# Power_Supply_Schematic.net
KiCad netlist of a schematic drawn in Altium Designer
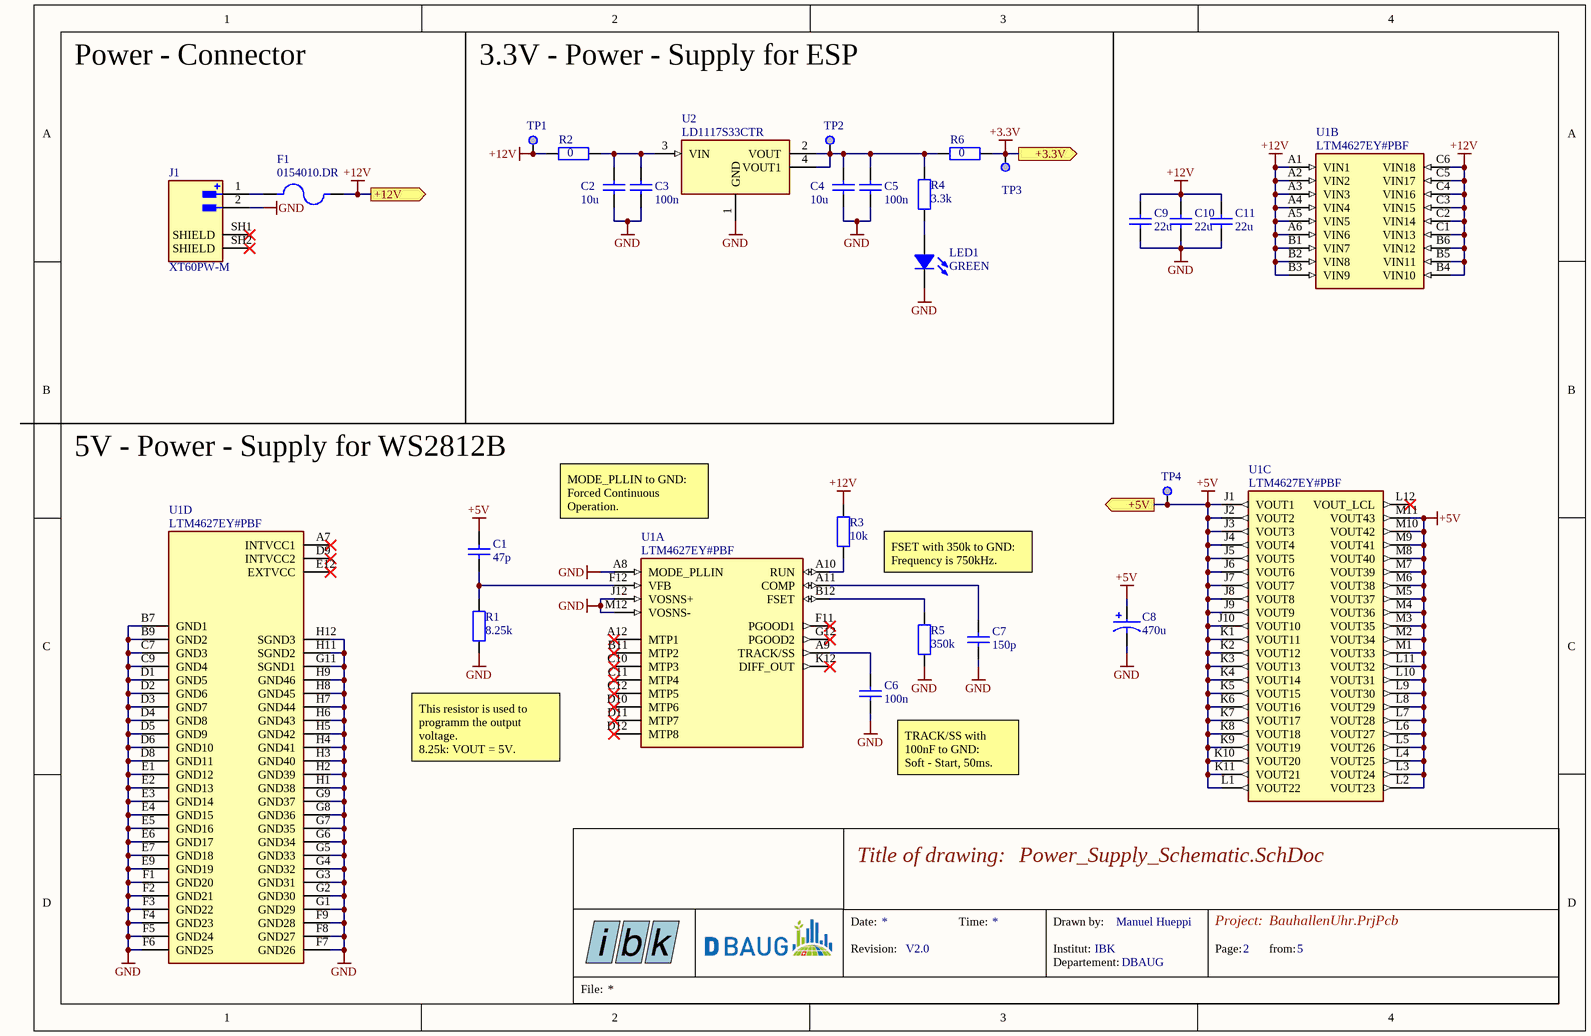
[diagram p0: Power_Supply_Schematic.SchDoc]

(export (version "E")
  (design (tool "Eeschema 10.0.6"))
  (components
    (comp (ref "C1")
      (value "47p")
      (footprint "PCB_Altium_Library_Manuel:0603_CAPACITOR")
      (description "0603")
      (libsource (lib "Schematic_Altium_Library_Manuel") (part "Capacitor"))
    )
    (comp (ref "C2")
      (value "10u")
      (footprint "PCB_Altium_Library_Manuel:Capacitor_0805")
      (description "0805")
      (libsource (lib "Schematic_Altium_Library_Manuel") (part "Capacitor_0805"))
    )
    (comp (ref "C3")
      (value "100n")
      (footprint "PCB_Altium_Library_Manuel:0603_CAPACITOR")
      (description "0603")
      (libsource (lib "Schematic_Altium_Library_Manuel") (part "Capacitor"))
    )
    (comp (ref "C4")
      (value "10u")
      (footprint "PCB_Altium_Library_Manuel:Capacitor_0805")
      (description "0805")
      (libsource (lib "Schematic_Altium_Library_Manuel") (part "Capacitor_0805"))
    )
    (comp (ref "C5")
      (value "100n")
      (footprint "PCB_Altium_Library_Manuel:0603_CAPACITOR")
      (description "0603")
      (libsource (lib "Schematic_Altium_Library_Manuel") (part "Capacitor"))
    )
    (comp (ref "C6")
      (value "100n")
      (footprint "PCB_Altium_Library_Manuel:0603_CAPACITOR")
      (description "0603")
      (libsource (lib "Schematic_Altium_Library_Manuel") (part "Capacitor"))
    )
    (comp (ref "C7")
      (value "150p")
      (footprint "PCB_Altium_Library_Manuel:0603_CAPACITOR")
      (description "0603")
      (libsource (lib "Schematic_Altium_Library_Manuel") (part "Capacitor"))
    )
    (comp (ref "C8")
      (value "470u")
      (footprint "PCB_Altium_Library_Manuel:Capacitor_Tantalum")
      (description "470 µF Molded Tantalum Capacitors 6.3 V 2917 (7343 Metric) 100mOhm.")
      (libsource (lib "Schematic_Altium_Library_Manuel") (part "Capacitor_Tantalum"))
    )
    (comp (ref "C9")
      (value "22u")
      (footprint "PCB_Altium_Library_Manuel:Capacitor_0805")
      (description "0805")
      (libsource (lib "Schematic_Altium_Library_Manuel") (part "Capacitor_0805"))
    )
    (comp (ref "C10")
      (value "22u")
      (footprint "PCB_Altium_Library_Manuel:Capacitor_0805")
      (description "0805")
      (libsource (lib "Schematic_Altium_Library_Manuel") (part "Capacitor_0805"))
    )
    (comp (ref "C11")
      (value "22u")
      (footprint "PCB_Altium_Library_Manuel:Capacitor_0805")
      (description "0805")
      (libsource (lib "Schematic_Altium_Library_Manuel") (part "Capacitor_0805"))
    )
    (comp (ref "F1")
      (value "0154010.DR")
      (footprint "PCB_Altium_Library_Manuel:Fuse")
      (description "FUSE BRD MNT 10A 125VAC/VDC SMD ¦ Littelfuse 0154010.DR.")
      (libsource (lib "Schematic_Altium_Library_Manuel") (part "Fuse"))
    )
    (comp (ref "J1")
      (value "XT60PW-M")
      (footprint "PCB_Altium_Library_Manuel:PCB_Connector")
      (description "Socket, DC supply, male, PIN: 2.")
      (fields (field (name "MF") "AMASS"))
      (libsource (lib "Schematic_Altium_Library_Manuel") (part "PCB_Connector"))
    )
    (comp (ref "LED1")
      (value "GREEN")
      (footprint "PCB_Altium_Library_Manuel:LED_0603, GREEN")
      (description "LED 0603, Green, 3.2 V, 20 mA, 430 mcd")
      (libsource (lib "Schematic_Altium_Library_Manuel") (part "LED_0603, GREEN"))
    )
    (comp (ref "R1")
      (value "8.25k")
      (footprint "PCB_Altium_Library_Manuel:Resistor_0603")
      (description "0603")
      (libsource (lib "Schematic_Altium_Library_Manuel") (part "Resistor_0603"))
    )
    (comp (ref "R2")
      (value "0")
      (footprint "PCB_Altium_Library_Manuel:1206_Resistor")
      (description "1206")
      (libsource (lib "Schematic_Altium_Library_Manuel") (part "Resistor_1206"))
    )
    (comp (ref "R3")
      (value "10k")
      (footprint "PCB_Altium_Library_Manuel:Resistor_0603")
      (description "0603")
      (libsource (lib "Schematic_Altium_Library_Manuel") (part "Resistor_0603"))
    )
    (comp (ref "R4")
      (value "3.3k")
      (footprint "PCB_Altium_Library_Manuel:Resistor_0603")
      (description "0603")
      (libsource (lib "Schematic_Altium_Library_Manuel") (part "Resistor_0603"))
    )
    (comp (ref "R5")
      (value "350k")
      (footprint "PCB_Altium_Library_Manuel:Resistor_0603")
      (description "0603")
      (libsource (lib "Schematic_Altium_Library_Manuel") (part "Resistor_0603"))
    )
    (comp (ref "R6")
      (value "0")
      (footprint "PCB_Altium_Library_Manuel:1206_Resistor")
      (description "1206")
      (libsource (lib "Schematic_Altium_Library_Manuel") (part "Resistor_1206"))
    )
    (comp (ref "TP1")
      (value "Testpoint S2761-46R")
      (footprint "PCB_Altium_Library_Manuel:Testpoint S2761-46R")
      (description "Prüfstecker und Messbuchsen EZ BoardWare S27 SMT Mini Test Terminal, Reel")
      (libsource (lib "Schematic_Altium_Library_Manuel") (part "Testpoint S2761-46R"))
    )
    (comp (ref "TP2")
      (value "Testpoint S2761-46R")
      (footprint "PCB_Altium_Library_Manuel:Testpoint S2761-46R")
      (description "Prüfstecker und Messbuchsen EZ BoardWare S27 SMT Mini Test Terminal, Reel")
      (libsource (lib "Schematic_Altium_Library_Manuel") (part "Testpoint S2761-46R"))
    )
    (comp (ref "TP3")
      (value "Testpoint S2761-46R")
      (footprint "PCB_Altium_Library_Manuel:Testpoint S2761-46R")
      (description "Prüfstecker und Messbuchsen EZ BoardWare S27 SMT Mini Test Terminal, Reel")
      (libsource (lib "Schematic_Altium_Library_Manuel") (part "Testpoint S2761-46R"))
    )
    (comp (ref "TP4")
      (value "Testpoint S2761-46R")
      (footprint "PCB_Altium_Library_Manuel:Testpoint S2761-46R")
      (description "Prüfstecker und Messbuchsen EZ BoardWare S27 SMT Mini Test Terminal, Reel")
      (libsource (lib "Schematic_Altium_Library_Manuel") (part "Testpoint S2761-46R"))
    )
    (comp (ref "U1")
      (value "LTM4627EY#PBF")
      (footprint "PCB_Altium_Library_Manuel:DCDC_Converter")
      (description "Module DC-DC 1-OUT 0.6V to 5V 15A Automotive 133-Pin BGA Tray.")
      (fields (field (name "MF") "Analog Devices"))
      (libsource (lib "Schematic_Altium_Library_Manuel") (part "DCDC_Converter"))
    )
    (comp (ref "U2")
      (value "LD1117S33CTR")
      (footprint "PCB_Altium_Library_Manuel:LD1117S33CTR")
      (description "LDO, 3.3V and 800mA.")
      (libsource (lib "Schematic_Altium_Library_Manuel") (part "LD1117S33CTR"))
    )
  )
  (nets
    (net (code "1") (name "+3.3V") (class "Default")
      (node (ref "R6") (pin "2") (pinfunction "2_2") (pintype "passive"))
      (node (ref "TP3") (pin "1") (pinfunction "1_1") (pintype "passive"))
    )
    (net (code "2") (name "+5V") (class "Default")
      (node (ref "C1") (pin "2") (pinfunction "2_2") (pintype "passive"))
      (node (ref "C8") (pin "1") (pinfunction "1_1") (pintype "passive"))
      (node (ref "TP4") (pin "1") (pinfunction "1_1") (pintype "passive"))
      (node (ref "U1") (pin "J1") (pinfunction "VOUT1_J1") (pintype "output"))
      (node (ref "U1") (pin "J10") (pinfunction "VOUT10_J10") (pintype "output"))
      (node (ref "U1") (pin "J2") (pinfunction "VOUT2_J2") (pintype "output"))
      (node (ref "U1") (pin "J3") (pinfunction "VOUT3_J3") (pintype "output"))
      (node (ref "U1") (pin "J4") (pinfunction "VOUT4_J4") (pintype "output"))
      (node (ref "U1") (pin "J5") (pinfunction "VOUT5_J5") (pintype "output"))
      (node (ref "U1") (pin "J6") (pinfunction "VOUT6_J6") (pintype "output"))
      (node (ref "U1") (pin "J7") (pinfunction "VOUT7_J7") (pintype "output"))
      (node (ref "U1") (pin "J8") (pinfunction "VOUT8_J8") (pintype "output"))
      (node (ref "U1") (pin "J9") (pinfunction "VOUT9_J9") (pintype "output"))
      (node (ref "U1") (pin "K1") (pinfunction "VOUT11_K1") (pintype "output"))
      (node (ref "U1") (pin "K10") (pinfunction "VOUT20_K10") (pintype "output"))
      (node (ref "U1") (pin "K11") (pinfunction "VOUT21_K11") (pintype "output"))
      (node (ref "U1") (pin "K2") (pinfunction "VOUT12_K2") (pintype "output"))
      (node (ref "U1") (pin "K3") (pinfunction "VOUT13_K3") (pintype "output"))
      (node (ref "U1") (pin "K4") (pinfunction "VOUT14_K4") (pintype "output"))
      (node (ref "U1") (pin "K5") (pinfunction "VOUT15_K5") (pintype "output"))
      (node (ref "U1") (pin "K6") (pinfunction "VOUT16_K6") (pintype "output"))
      (node (ref "U1") (pin "K7") (pinfunction "VOUT17_K7") (pintype "output"))
      (node (ref "U1") (pin "K8") (pinfunction "VOUT18_K8") (pintype "output"))
      (node (ref "U1") (pin "K9") (pinfunction "VOUT19_K9") (pintype "output"))
      (node (ref "U1") (pin "L1") (pinfunction "VOUT22_L1") (pintype "output"))
      (node (ref "U1") (pin "L10") (pinfunction "VOUT31_L10") (pintype "output"))
      (node (ref "U1") (pin "L11") (pinfunction "VOUT32_L11") (pintype "output"))
      (node (ref "U1") (pin "L2") (pinfunction "VOUT23_L2") (pintype "output"))
      (node (ref "U1") (pin "L3") (pinfunction "VOUT24_L3") (pintype "output"))
      (node (ref "U1") (pin "L4") (pinfunction "VOUT25_L4") (pintype "output"))
      (node (ref "U1") (pin "L5") (pinfunction "VOUT26_L5") (pintype "output"))
      (node (ref "U1") (pin "L6") (pinfunction "VOUT27_L6") (pintype "output"))
      (node (ref "U1") (pin "L7") (pinfunction "VOUT28_L7") (pintype "output"))
      (node (ref "U1") (pin "L8") (pinfunction "VOUT29_L8") (pintype "output"))
      (node (ref "U1") (pin "L9") (pinfunction "VOUT30_L9") (pintype "output"))
      (node (ref "U1") (pin "M1") (pinfunction "VOUT33_M1") (pintype "output"))
      (node (ref "U1") (pin "M10") (pinfunction "VOUT42_M10") (pintype "output"))
      (node (ref "U1") (pin "M11") (pinfunction "VOUT43_M11") (pintype "output"))
      (node (ref "U1") (pin "M2") (pinfunction "VOUT34_M2") (pintype "output"))
      (node (ref "U1") (pin "M3") (pinfunction "VOUT35_M3") (pintype "output"))
      (node (ref "U1") (pin "M4") (pinfunction "VOUT36_M4") (pintype "output"))
      (node (ref "U1") (pin "M5") (pinfunction "VOUT37_M5") (pintype "output"))
      (node (ref "U1") (pin "M6") (pinfunction "VOUT38_M6") (pintype "output"))
      (node (ref "U1") (pin "M7") (pinfunction "VOUT39_M7") (pintype "output"))
      (node (ref "U1") (pin "M8") (pinfunction "VOUT40_M8") (pintype "output"))
      (node (ref "U1") (pin "M9") (pinfunction "VOUT41_M9") (pintype "output"))
    )
    (net (code "3") (name "+12V") (class "Default")
      (node (ref "C10") (pin "2") (pinfunction "2_2") (pintype "passive"))
      (node (ref "C11") (pin "2") (pinfunction "2_2") (pintype "passive"))
      (node (ref "C9") (pin "2") (pinfunction "2_2") (pintype "passive"))
      (node (ref "F1") (pin "2") (pinfunction "2_2") (pintype "passive"))
      (node (ref "R2") (pin "1") (pinfunction "1_1") (pintype "passive"))
      (node (ref "R3") (pin "2") (pinfunction "2_2") (pintype "passive"))
      (node (ref "TP1") (pin "1") (pinfunction "1_1") (pintype "passive"))
      (node (ref "U1") (pin "A1") (pinfunction "VIN1_A1") (pintype "input"))
      (node (ref "U1") (pin "A2") (pinfunction "VIN2_A2") (pintype "input"))
      (node (ref "U1") (pin "A3") (pinfunction "VIN3_A3") (pintype "input"))
      (node (ref "U1") (pin "A4") (pinfunction "VIN4_A4") (pintype "input"))
      (node (ref "U1") (pin "A5") (pinfunction "VIN5_A5") (pintype "input"))
      (node (ref "U1") (pin "A6") (pinfunction "VIN6_A6") (pintype "input"))
      (node (ref "U1") (pin "B1") (pinfunction "VIN7_B1") (pintype "input"))
      (node (ref "U1") (pin "B2") (pinfunction "VIN8_B2") (pintype "input"))
      (node (ref "U1") (pin "B3") (pinfunction "VIN9_B3") (pintype "input"))
      (node (ref "U1") (pin "B4") (pinfunction "VIN10_B4") (pintype "input"))
      (node (ref "U1") (pin "B5") (pinfunction "VIN11_B5") (pintype "input"))
      (node (ref "U1") (pin "B6") (pinfunction "VIN12_B6") (pintype "input"))
      (node (ref "U1") (pin "C1") (pinfunction "VIN13_C1") (pintype "input"))
      (node (ref "U1") (pin "C2") (pinfunction "VIN14_C2") (pintype "input"))
      (node (ref "U1") (pin "C3") (pinfunction "VIN15_C3") (pintype "input"))
      (node (ref "U1") (pin "C4") (pinfunction "VIN16_C4") (pintype "input"))
      (node (ref "U1") (pin "C5") (pinfunction "VIN17_C5") (pintype "input"))
      (node (ref "U1") (pin "C6") (pinfunction "VIN18_C6") (pintype "input"))
    )
    (net (code "4") (name "GND") (class "Default")
      (node (ref "C10") (pin "1") (pinfunction "1_1") (pintype "passive"))
      (node (ref "C11") (pin "1") (pinfunction "1_1") (pintype "passive"))
      (node (ref "C2") (pin "1") (pinfunction "1_1") (pintype "passive"))
      (node (ref "C3") (pin "1") (pinfunction "1_1") (pintype "passive"))
      (node (ref "C4") (pin "1") (pinfunction "1_1") (pintype "passive"))
      (node (ref "C5") (pin "1") (pinfunction "1_1") (pintype "passive"))
      (node (ref "C6") (pin "1") (pinfunction "1_1") (pintype "passive"))
      (node (ref "C7") (pin "1") (pinfunction "1_1") (pintype "passive"))
      (node (ref "C8") (pin "2") (pinfunction "2_2") (pintype "passive"))
      (node (ref "C9") (pin "1") (pinfunction "1_1") (pintype "passive"))
      (node (ref "J1") (pin "2") (pinfunction "N_2") (pintype "passive"))
      (node (ref "LED1") (pin "K") (pinfunction "K_K") (pintype "passive"))
      (node (ref "R1") (pin "1") (pinfunction "1_1") (pintype "passive"))
      (node (ref "R5") (pin "1") (pinfunction "1_1") (pintype "passive"))
      (node (ref "U1") (pin "A8") (pinfunction "MODE_PLLIN_A8") (pintype "input"))
      (node (ref "U1") (pin "B7") (pinfunction "GND1_B7") (pintype "power_in"))
      (node (ref "U1") (pin "B9") (pinfunction "GND2_B9") (pintype "power_in"))
      (node (ref "U1") (pin "C7") (pinfunction "GND3_C7") (pintype "power_in"))
      (node (ref "U1") (pin "C9") (pinfunction "GND4_C9") (pintype "power_in"))
      (node (ref "U1") (pin "D1") (pinfunction "GND5_D1") (pintype "power_in"))
      (node (ref "U1") (pin "D2") (pinfunction "GND6_D2") (pintype "power_in"))
      (node (ref "U1") (pin "D3") (pinfunction "GND7_D3") (pintype "power_in"))
      (node (ref "U1") (pin "D4") (pinfunction "GND8_D4") (pintype "power_in"))
      (node (ref "U1") (pin "D5") (pinfunction "GND9_D5") (pintype "power_in"))
      (node (ref "U1") (pin "D6") (pinfunction "GND10_D6") (pintype "power_in"))
      (node (ref "U1") (pin "D8") (pinfunction "GND11_D8") (pintype "power_in"))
      (node (ref "U1") (pin "E1") (pinfunction "GND12_E1") (pintype "power_in"))
      (node (ref "U1") (pin "E2") (pinfunction "GND13_E2") (pintype "power_in"))
      (node (ref "U1") (pin "E3") (pinfunction "GND14_E3") (pintype "power_in"))
      (node (ref "U1") (pin "E4") (pinfunction "GND15_E4") (pintype "power_in"))
      (node (ref "U1") (pin "E5") (pinfunction "GND16_E5") (pintype "power_in"))
      (node (ref "U1") (pin "E6") (pinfunction "GND17_E6") (pintype "power_in"))
      (node (ref "U1") (pin "E7") (pinfunction "GND18_E7") (pintype "power_in"))
      (node (ref "U1") (pin "E9") (pinfunction "GND19_E9") (pintype "power_in"))
      (node (ref "U1") (pin "F1") (pinfunction "GND20_F1") (pintype "power_in"))
      (node (ref "U1") (pin "F2") (pinfunction "GND21_F2") (pintype "power_in"))
      (node (ref "U1") (pin "F3") (pinfunction "GND22_F3") (pintype "power_in"))
      (node (ref "U1") (pin "F4") (pinfunction "GND23_F4") (pintype "power_in"))
      (node (ref "U1") (pin "F5") (pinfunction "GND24_F5") (pintype "power_in"))
      (node (ref "U1") (pin "F6") (pinfunction "GND25_F6") (pintype "power_in"))
      (node (ref "U1") (pin "F7") (pinfunction "GND26_F7") (pintype "power_in"))
      (node (ref "U1") (pin "F8") (pinfunction "GND27_F8") (pintype "power_in"))
      (node (ref "U1") (pin "F9") (pinfunction "GND28_F9") (pintype "power_in"))
      (node (ref "U1") (pin "G1") (pinfunction "GND29_G1") (pintype "power_in"))
      (node (ref "U1") (pin "G11") (pinfunction "SGND1_G11") (pintype "power_in"))
      (node (ref "U1") (pin "G2") (pinfunction "GND30_G2") (pintype "power_in"))
      (node (ref "U1") (pin "G3") (pinfunction "GND31_G3") (pintype "power_in"))
      (node (ref "U1") (pin "G4") (pinfunction "GND32_G4") (pintype "power_in"))
      (node (ref "U1") (pin "G5") (pinfunction "GND33_G5") (pintype "power_in"))
      (node (ref "U1") (pin "G6") (pinfunction "GND34_G6") (pintype "power_in"))
      (node (ref "U1") (pin "G7") (pinfunction "GND35_G7") (pintype "power_in"))
      (node (ref "U1") (pin "G8") (pinfunction "GND36_G8") (pintype "power_in"))
      (node (ref "U1") (pin "G9") (pinfunction "GND37_G9") (pintype "power_in"))
      (node (ref "U1") (pin "H1") (pinfunction "GND38_H1") (pintype "power_in"))
      (node (ref "U1") (pin "H11") (pinfunction "SGND2_H11") (pintype "power_in"))
      (node (ref "U1") (pin "H12") (pinfunction "SGND3_H12") (pintype "power_in"))
      (node (ref "U1") (pin "H2") (pinfunction "GND39_H2") (pintype "power_in"))
      (node (ref "U1") (pin "H3") (pinfunction "GND40_H3") (pintype "power_in"))
      (node (ref "U1") (pin "H4") (pinfunction "GND41_H4") (pintype "power_in"))
      (node (ref "U1") (pin "H5") (pinfunction "GND42_H5") (pintype "power_in"))
      (node (ref "U1") (pin "H6") (pinfunction "GND43_H6") (pintype "power_in"))
      (node (ref "U1") (pin "H7") (pinfunction "GND44_H7") (pintype "power_in"))
      (node (ref "U1") (pin "H8") (pinfunction "GND45_H8") (pintype "power_in"))
      (node (ref "U1") (pin "H9") (pinfunction "GND46_H9") (pintype "power_in"))
      (node (ref "U1") (pin "J12") (pinfunction "VOSNS+_J12") (pintype "input"))
      (node (ref "U1") (pin "M12") (pinfunction "VOSNS-_M12") (pintype "input"))
      (node (ref "U2") (pin "1") (pinfunction "GND_1") (pintype "power_in"))
    )
    (net (code "5") (name "Net-(J1-P)") (class "Default")
      (node (ref "F1") (pin "1") (pinfunction "1_1") (pintype "passive"))
      (node (ref "J1") (pin "1") (pinfunction "P_1") (pintype "passive"))
    )
    (net (code "6") (name "Net-(LED1-PadA)") (class "Default")
      (node (ref "LED1") (pin "A") (pinfunction "A_A") (pintype "passive"))
      (node (ref "R4") (pin "1") (pinfunction "1_1") (pintype "passive"))
    )
    (net (code "7") (name "Net-(U1A-COMP)") (class "Default")
      (node (ref "C7") (pin "2") (pinfunction "2_2") (pintype "passive"))
      (node (ref "U1") (pin "A11") (pinfunction "COMP_A11") (pintype "bidirectional"))
    )
    (net (code "8") (name "Net-(U1A-FSET)") (class "Default")
      (node (ref "R5") (pin "2") (pinfunction "2_2") (pintype "passive"))
      (node (ref "U1") (pin "B12") (pinfunction "FSET_B12") (pintype "bidirectional"))
    )
    (net (code "9") (name "Net-(U1A-RUN)") (class "Default")
      (node (ref "R3") (pin "1") (pinfunction "1_1") (pintype "passive"))
      (node (ref "U1") (pin "A10") (pinfunction "RUN_A10") (pintype "bidirectional"))
    )
    (net (code "10") (name "Net-(U1A-TRACK{slash}SS)") (class "Default")
      (node (ref "C6") (pin "2") (pinfunction "2_2") (pintype "passive"))
      (node (ref "U1") (pin "A9") (pinfunction "TRACK/SS_A9") (pintype "output"))
    )
    (net (code "11") (name "Net-(U1A-VFB)") (class "Default")
      (node (ref "C1") (pin "1") (pinfunction "1_1") (pintype "passive"))
      (node (ref "R1") (pin "2") (pinfunction "2_2") (pintype "passive"))
      (node (ref "U1") (pin "F12") (pinfunction "VFB_F12") (pintype "input"))
    )
    (net (code "12") (name "Net-(U2-VIN)") (class "Default")
      (node (ref "C2") (pin "2") (pinfunction "2_2") (pintype "passive"))
      (node (ref "C3") (pin "2") (pinfunction "2_2") (pintype "passive"))
      (node (ref "R2") (pin "2") (pinfunction "2_2") (pintype "passive"))
      (node (ref "U2") (pin "3") (pinfunction "VIN_3") (pintype "input"))
    )
    (net (code "13") (name "Net-(U2-VOUT)") (class "Default")
      (node (ref "C4") (pin "2") (pinfunction "2_2") (pintype "passive"))
      (node (ref "C5") (pin "2") (pinfunction "2_2") (pintype "passive"))
      (node (ref "R4") (pin "2") (pinfunction "2_2") (pintype "passive"))
      (node (ref "R6") (pin "1") (pinfunction "1_1") (pintype "passive"))
      (node (ref "TP2") (pin "1") (pinfunction "1_1") (pintype "passive"))
      (node (ref "U2") (pin "2") (pinfunction "VOUT_2") (pintype "power_in"))
      (node (ref "U2") (pin "4") (pinfunction "VOUT1_4") (pintype "power_in"))
    )
    (net (code "14") (name "unconnected-(J1-SHIELD-PadSH1)") (class "Default")
      (node (ref "J1") (pin "SH1") (pinfunction "SHIELD_SH1") (pintype "passive+no_connect"))
    )
    (net (code "15") (name "unconnected-(J1-SHIELD-PadSH2)") (class "Default")
      (node (ref "J1") (pin "SH2") (pinfunction "SHIELD_SH2") (pintype "passive+no_connect"))
    )
    (net (code "16") (name "unconnected-(U1A-DIFF_OUT-PadK12)") (class "Default")
      (node (ref "U1") (pin "K12") (pinfunction "DIFF_OUT_K12") (pintype "output+no_connect"))
    )
    (net (code "17") (name "unconnected-(U1A-MTP1-PadA12)") (class "Default")
      (node (ref "U1") (pin "A12") (pinfunction "MTP1_A12") (pintype "passive+no_connect"))
    )
    (net (code "18") (name "unconnected-(U1A-MTP2-PadB11)") (class "Default")
      (node (ref "U1") (pin "B11") (pinfunction "MTP2_B11") (pintype "passive+no_connect"))
    )
    (net (code "19") (name "unconnected-(U1A-MTP3-PadC10)") (class "Default")
      (node (ref "U1") (pin "C10") (pinfunction "MTP3_C10") (pintype "passive+no_connect"))
    )
    (net (code "20") (name "unconnected-(U1A-MTP4-PadC11)") (class "Default")
      (node (ref "U1") (pin "C11") (pinfunction "MTP4_C11") (pintype "passive+no_connect"))
    )
    (net (code "21") (name "unconnected-(U1A-MTP5-PadC12)") (class "Default")
      (node (ref "U1") (pin "C12") (pinfunction "MTP5_C12") (pintype "passive+no_connect"))
    )
    (net (code "22") (name "unconnected-(U1A-MTP6-PadD10)") (class "Default")
      (node (ref "U1") (pin "D10") (pinfunction "MTP6_D10") (pintype "passive+no_connect"))
    )
    (net (code "23") (name "unconnected-(U1A-MTP7-PadD11)") (class "Default")
      (node (ref "U1") (pin "D11") (pinfunction "MTP7_D11") (pintype "passive+no_connect"))
    )
    (net (code "24") (name "unconnected-(U1A-MTP8-PadD12)") (class "Default")
      (node (ref "U1") (pin "D12") (pinfunction "MTP8_D12") (pintype "passive+no_connect"))
    )
    (net (code "25") (name "unconnected-(U1A-PGOOD1-PadF11)") (class "Default")
      (node (ref "U1") (pin "F11") (pinfunction "PGOOD1_F11") (pintype "output+no_connect"))
    )
    (net (code "26") (name "unconnected-(U1A-PGOOD2-PadG12)") (class "Default")
      (node (ref "U1") (pin "G12") (pinfunction "PGOOD2_G12") (pintype "output+no_connect"))
    )
    (net (code "27") (name "unconnected-(U1C-VOUT_LCL-PadL12)") (class "Default")
      (node (ref "U1") (pin "L12") (pinfunction "VOUT_LCL_L12") (pintype "output+no_connect"))
    )
    (net (code "28") (name "unconnected-(U1D-EXTVCC-PadE12)") (class "Default")
      (node (ref "U1") (pin "E12") (pinfunction "EXTVCC_E12") (pintype "power_in+no_connect"))
    )
    (net (code "29") (name "unconnected-(U1D-INTVCC1-PadA7)") (class "Default")
      (node (ref "U1") (pin "A7") (pinfunction "INTVCC1_A7") (pintype "power_in+no_connect"))
    )
    (net (code "30") (name "unconnected-(U1D-INTVCC2-PadD9)") (class "Default")
      (node (ref "U1") (pin "D9") (pinfunction "INTVCC2_D9") (pintype "power_in+no_connect"))
    )
  )
)
